# debug01.net
KiCad netlist of a schematic drawn in EAGLE
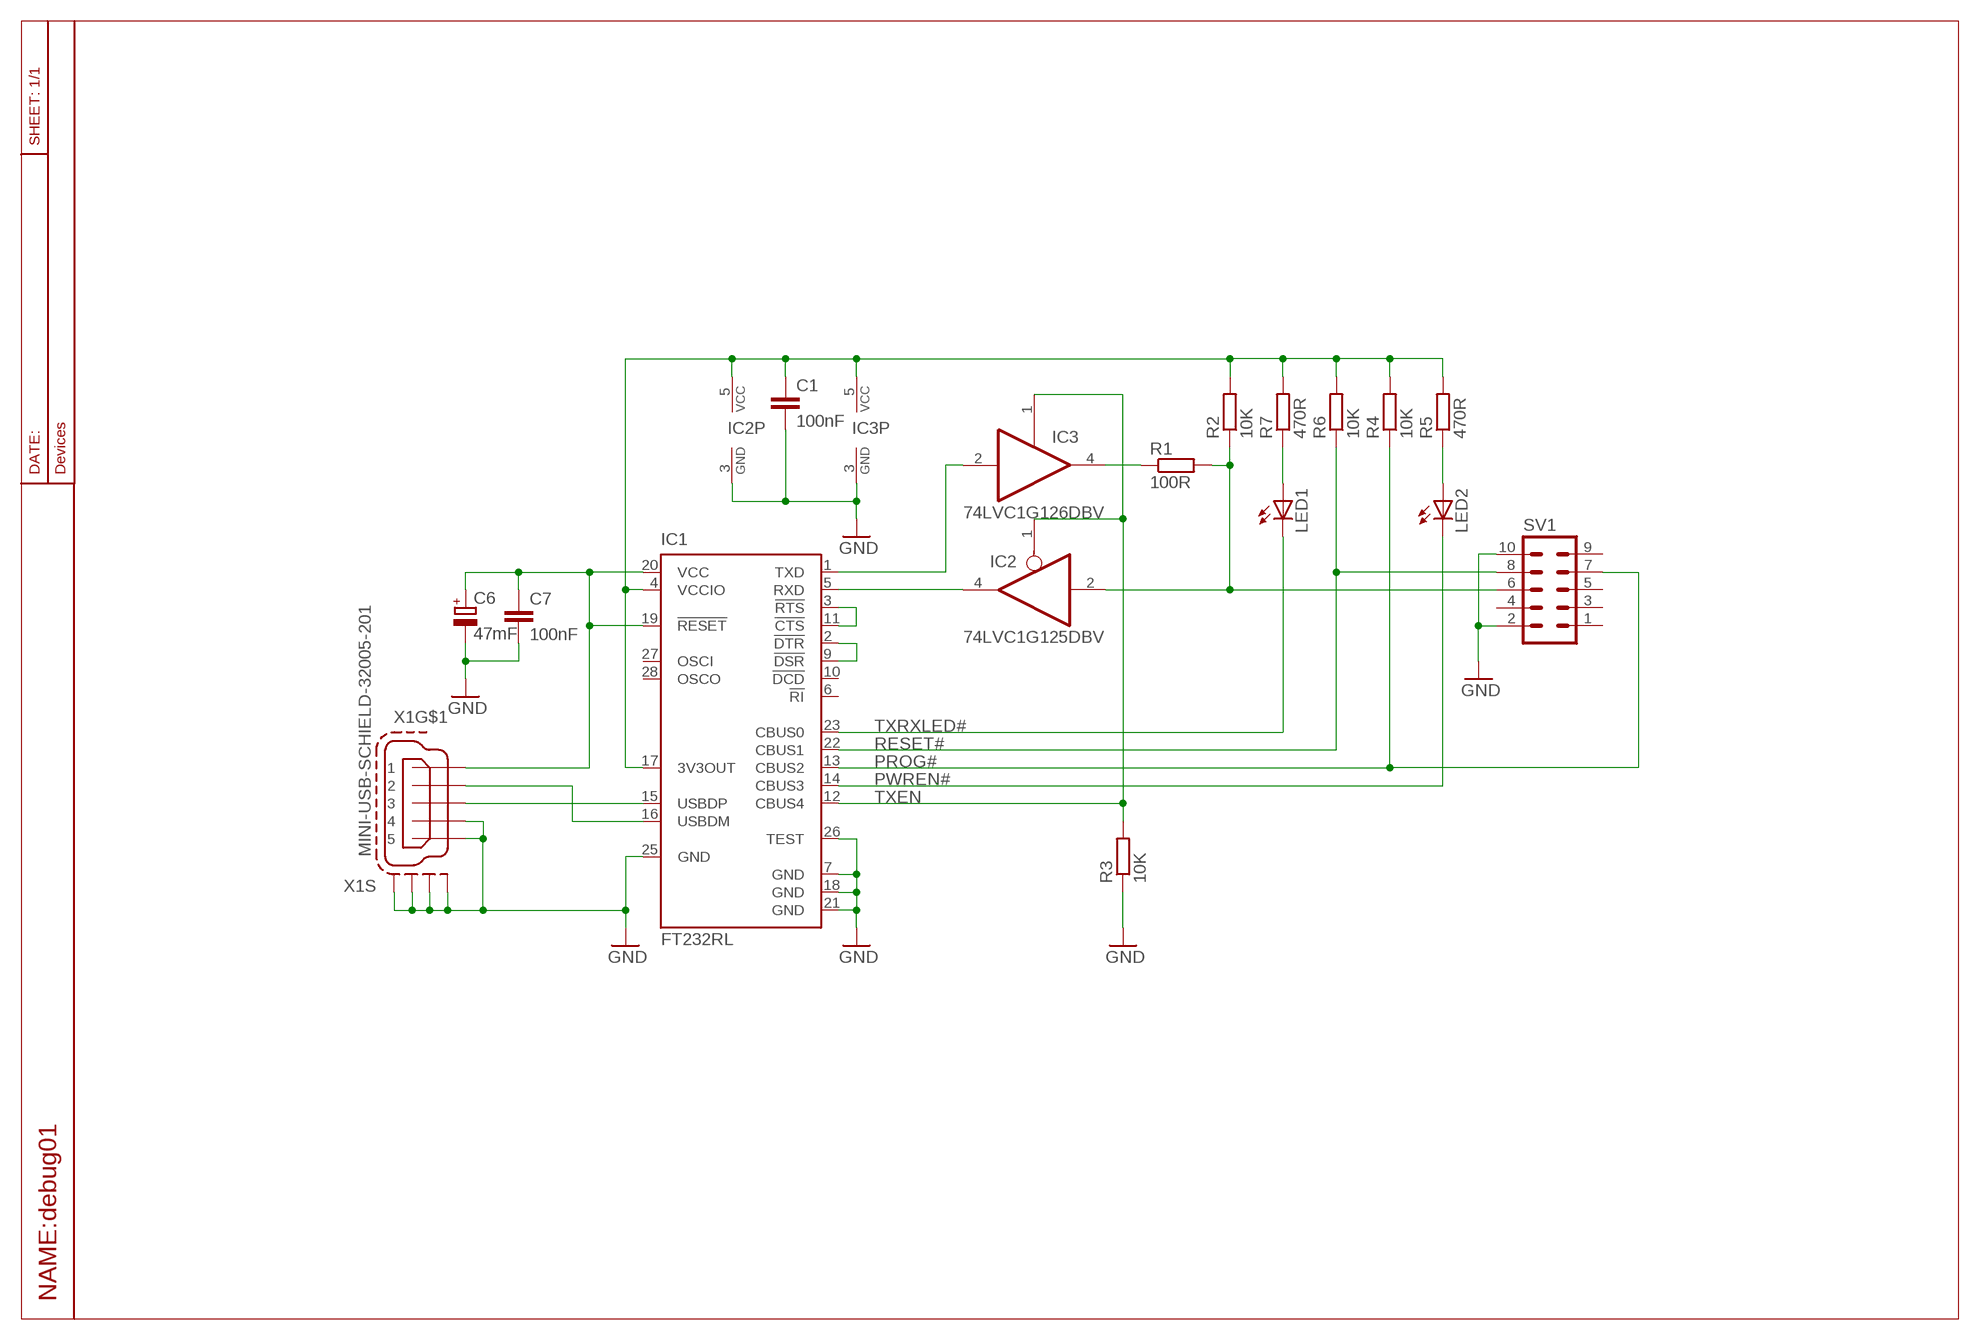
[diagram p0: schematic, sheet 1]

(export (version "E")
  (design (tool "Eeschema 10.0.6"))
  (components
    (comp (ref "C1")
      (value "100nF")
      (footprint "eagle-import:C0603")
      (libsource (lib "eagle-import") (part "C-EUC0603"))
    )
    (comp (ref "C6")
      (value "47mF")
      (footprint "eagle-import:CT3528")
      (libsource (lib "eagle-import") (part "CPOL-EUCT3528"))
    )
    (comp (ref "C7")
      (value "100nF")
      (footprint "eagle-import:C0603")
      (libsource (lib "eagle-import") (part "C-EUC0603"))
    )
    (comp (ref "IC1")
      (value "FT232RL")
      (footprint "eagle-import:SSOP28")
      (libsource (lib "eagle-import") (part "FT232RL"))
    )
    (comp (ref "IC2")
      (value "74LVC1G125DBV")
      (footprint "eagle-import:SOT23-5")
      (libsource (lib "eagle-import") (part "741G125DBVLVC"))
    )
    (comp (ref "IC3")
      (value "74LVC1G126DBV")
      (footprint "eagle-import:SOT23-5")
      (libsource (lib "eagle-import") (part "741G126DBVLVC"))
    )
    (comp (ref "LED1")
      (value "LEDCHIPLED_0805")
      (footprint "eagle-import:CHIPLED_0805")
      (libsource (lib "eagle-import") (part "LEDCHIPLED_0805"))
    )
    (comp (ref "LED2")
      (value "LEDCHIPLED_0805")
      (footprint "eagle-import:CHIPLED_0805")
      (libsource (lib "eagle-import") (part "LEDCHIPLED_0805"))
    )
    (comp (ref "R1")
      (value "100R")
      (footprint "eagle-import:R0603")
      (libsource (lib "eagle-import") (part "R-EU_R0603"))
    )
    (comp (ref "R2")
      (value "10K")
      (footprint "eagle-import:R0603")
      (libsource (lib "eagle-import") (part "R-EU_R0603"))
    )
    (comp (ref "R3")
      (value "10K")
      (footprint "eagle-import:R1206")
      (libsource (lib "eagle-import") (part "R-EU_R1206"))
    )
    (comp (ref "R4")
      (value "10K")
      (footprint "eagle-import:R0603")
      (libsource (lib "eagle-import") (part "R-EU_R0603"))
    )
    (comp (ref "R5")
      (value "470R")
      (footprint "eagle-import:R0603")
      (libsource (lib "eagle-import") (part "R-EU_R0603"))
    )
    (comp (ref "R6")
      (value "10K")
      (footprint "eagle-import:R0603")
      (libsource (lib "eagle-import") (part "R-EU_R0603"))
    )
    (comp (ref "R7")
      (value "470R")
      (footprint "eagle-import:R0603")
      (libsource (lib "eagle-import") (part "R-EU_R0603"))
    )
    (comp (ref "SV1")
      (value "ML10")
      (footprint "eagle-import:ML10")
      (libsource (lib "eagle-import") (part "ML10"))
    )
    (comp (ref "X1")
      (value "MINI-USB-SCHIELD-32005-201")
      (footprint "eagle-import:32005-201")
      (libsource (lib "eagle-import") (part "MINI-USB-SCHIELD-32005-201"))
    )
  )
  (nets
    (net (code "1") (name "/PROG#") (class "Default")
      (node (ref "IC1") (pin "13") (pinfunction "CBUS2_13") (pintype "bidirectional"))
      (node (ref "R4") (pin "1") (pinfunction "1_1") (pintype "passive"))
      (node (ref "SV1") (pin "7") (pinfunction "7_7") (pintype "passive"))
    )
    (net (code "2") (name "/PWREN#") (class "Default")
      (node (ref "IC1") (pin "14") (pinfunction "CBUS3_14") (pintype "bidirectional"))
      (node (ref "LED2") (pin "C") (pinfunction "C_C") (pintype "passive"))
    )
    (net (code "3") (name "/RESET#") (class "Default")
      (node (ref "IC1") (pin "22") (pinfunction "CBUS1_22") (pintype "bidirectional"))
      (node (ref "R6") (pin "1") (pinfunction "1_1") (pintype "passive"))
      (node (ref "SV1") (pin "8") (pinfunction "8_8") (pintype "passive"))
    )
    (net (code "4") (name "/TXEN") (class "Default")
      (node (ref "IC1") (pin "12") (pinfunction "CBUS4_12") (pintype "bidirectional"))
      (node (ref "IC2") (pin "1") (pinfunction "OE_1") (pintype "input"))
      (node (ref "IC3") (pin "1") (pinfunction "OE_1") (pintype "input"))
      (node (ref "R3") (pin "2") (pinfunction "2_2") (pintype "passive"))
    )
    (net (code "5") (name "/TXRXLED#") (class "Default")
      (node (ref "IC1") (pin "23") (pinfunction "CBUS0_23") (pintype "bidirectional"))
      (node (ref "LED1") (pin "C") (pinfunction "C_C") (pintype "passive"))
    )
    (net (code "6") (name "GND") (class "Default")
      (node (ref "C1") (pin "2") (pinfunction "2_2") (pintype "passive"))
      (node (ref "C6") (pin "-") (pinfunction "-_-") (pintype "passive"))
      (node (ref "C7") (pin "2") (pinfunction "2_2") (pintype "passive"))
      (node (ref "IC1") (pin "18") (pinfunction "GND_18") (pintype "power_in"))
      (node (ref "IC1") (pin "21") (pinfunction "GND_21") (pintype "power_in"))
      (node (ref "IC1") (pin "25") (pinfunction "GND_25") (pintype "power_in"))
      (node (ref "IC1") (pin "26") (pinfunction "TEST_26") (pintype "input"))
      (node (ref "IC1") (pin "7") (pinfunction "GND_7") (pintype "power_in"))
      (node (ref "IC2") (pin "3") (pinfunction "GND_3") (pintype "power_in"))
      (node (ref "IC3") (pin "3") (pinfunction "GND_3") (pintype "power_in"))
      (node (ref "R3") (pin "1") (pinfunction "1_1") (pintype "passive"))
      (node (ref "SV1") (pin "10") (pinfunction "10_10") (pintype "passive"))
      (node (ref "SV1") (pin "2") (pinfunction "2_2") (pintype "passive"))
      (node (ref "X1") (pin "4") (pinfunction "4_4") (pintype "passive"))
      (node (ref "X1") (pin "5") (pinfunction "5_5") (pintype "passive"))
      (node (ref "X1") (pin "M1") (pinfunction "S1_M1") (pintype "passive"))
      (node (ref "X1") (pin "M2") (pinfunction "S2_M2") (pintype "passive"))
      (node (ref "X1") (pin "M3") (pinfunction "S3_M3") (pintype "passive"))
      (node (ref "X1") (pin "M4") (pinfunction "S4_M4") (pintype "passive"))
    )
    (net (code "7") (name "Net-(IC1-3V3OUT)") (class "Default")
      (node (ref "C1") (pin "1") (pinfunction "1_1") (pintype "passive"))
      (node (ref "IC1") (pin "17") (pinfunction "3V3OUT_17") (pintype "output"))
      (node (ref "IC1") (pin "4") (pinfunction "VCCIO_4") (pintype "power_in"))
      (node (ref "IC2") (pin "5") (pinfunction "VCC_5") (pintype "power_in"))
      (node (ref "IC3") (pin "5") (pinfunction "VCC_5") (pintype "power_in"))
      (node (ref "R2") (pin "2") (pinfunction "2_2") (pintype "passive"))
      (node (ref "R4") (pin "2") (pinfunction "2_2") (pintype "passive"))
      (node (ref "R5") (pin "2") (pinfunction "2_2") (pintype "passive"))
      (node (ref "R6") (pin "2") (pinfunction "2_2") (pintype "passive"))
      (node (ref "R7") (pin "2") (pinfunction "2_2") (pintype "passive"))
    )
    (net (code "8") (name "Net-(IC1-RXD)") (class "Default")
      (node (ref "IC1") (pin "5") (pinfunction "RXD_5") (pintype "input"))
      (node (ref "IC2") (pin "4") (pinfunction "O_4") (pintype "tri_state"))
    )
    (net (code "9") (name "Net-(IC1-TXD)") (class "Default")
      (node (ref "IC1") (pin "1") (pinfunction "TXD_1") (pintype "output"))
      (node (ref "IC3") (pin "2") (pinfunction "I_2") (pintype "input"))
    )
    (net (code "10") (name "Net-(IC1-USBDM)") (class "Default")
      (node (ref "IC1") (pin "16") (pinfunction "USBDM_16") (pintype "bidirectional"))
      (node (ref "X1") (pin "2") (pinfunction "2_2") (pintype "passive"))
    )
    (net (code "11") (name "Net-(IC1-USBDP)") (class "Default")
      (node (ref "IC1") (pin "15") (pinfunction "USBDP_15") (pintype "bidirectional"))
      (node (ref "X1") (pin "3") (pinfunction "3_3") (pintype "passive"))
    )
    (net (code "12") (name "Net-(IC1-VCC)") (class "Default")
      (node (ref "C6") (pin "+") (pinfunction "+_+") (pintype "passive"))
      (node (ref "C7") (pin "1") (pinfunction "1_1") (pintype "passive"))
      (node (ref "IC1") (pin "19") (pinfunction "~{RESET}_19") (pintype "input"))
      (node (ref "IC1") (pin "20") (pinfunction "VCC_20") (pintype "power_in"))
      (node (ref "X1") (pin "1") (pinfunction "1_1") (pintype "passive"))
    )
    (net (code "13") (name "Net-(IC1-~{CTS})") (class "Default")
      (node (ref "IC1") (pin "11") (pinfunction "~{CTS}_11") (pintype "input"))
      (node (ref "IC1") (pin "3") (pinfunction "~{RTS}_3") (pintype "output"))
    )
    (net (code "14") (name "Net-(IC1-~{DSR})") (class "Default")
      (node (ref "IC1") (pin "2") (pinfunction "~{DTR}_2") (pintype "output"))
      (node (ref "IC1") (pin "9") (pinfunction "~{DSR}_9") (pintype "input"))
    )
    (net (code "15") (name "Net-(IC2A-I)") (class "Default")
      (node (ref "IC2") (pin "2") (pinfunction "I_2") (pintype "input"))
      (node (ref "R1") (pin "2") (pinfunction "2_2") (pintype "passive"))
      (node (ref "R2") (pin "1") (pinfunction "1_1") (pintype "passive"))
      (node (ref "SV1") (pin "6") (pinfunction "6_6") (pintype "passive"))
    )
    (net (code "16") (name "Net-(IC3A-O)") (class "Default")
      (node (ref "IC3") (pin "4") (pinfunction "O_4") (pintype "output"))
      (node (ref "R1") (pin "1") (pinfunction "1_1") (pintype "passive"))
    )
    (net (code "17") (name "Net-(LED1-PadA)") (class "Default")
      (node (ref "LED1") (pin "A") (pinfunction "A_A") (pintype "passive"))
      (node (ref "R7") (pin "1") (pinfunction "1_1") (pintype "passive"))
    )
    (net (code "18") (name "Net-(LED2-PadA)") (class "Default")
      (node (ref "LED2") (pin "A") (pinfunction "A_A") (pintype "passive"))
      (node (ref "R5") (pin "1") (pinfunction "1_1") (pintype "passive"))
    )
    (net (code "19") (name "unconnected-(IC1-OSCI-Pad27)") (class "Default")
      (node (ref "IC1") (pin "27") (pinfunction "OSCI_27") (pintype "input"))
    )
    (net (code "20") (name "unconnected-(IC1-OSCO-Pad28)") (class "Default")
      (node (ref "IC1") (pin "28") (pinfunction "OSCO_28") (pintype "output"))
    )
    (net (code "21") (name "unconnected-(IC1-~{DCD}-Pad10)") (class "Default")
      (node (ref "IC1") (pin "10") (pinfunction "~{DCD}_10") (pintype "input"))
    )
    (net (code "22") (name "unconnected-(IC1-~{RI}-Pad6)") (class "Default")
      (node (ref "IC1") (pin "6") (pinfunction "~{RI}_6") (pintype "input"))
    )
    (net (code "23") (name "unconnected-(SV1-Pad1)") (class "Default")
      (node (ref "SV1") (pin "1") (pinfunction "1_1") (pintype "passive"))
    )
    (net (code "24") (name "unconnected-(SV1-Pad3)") (class "Default")
      (node (ref "SV1") (pin "3") (pinfunction "3_3") (pintype "passive"))
    )
    (net (code "25") (name "unconnected-(SV1-Pad4)") (class "Default")
      (node (ref "SV1") (pin "4") (pinfunction "4_4") (pintype "passive"))
    )
    (net (code "26") (name "unconnected-(SV1-Pad5)") (class "Default")
      (node (ref "SV1") (pin "5") (pinfunction "5_5") (pintype "passive"))
    )
    (net (code "27") (name "unconnected-(SV1-Pad9)") (class "Default")
      (node (ref "SV1") (pin "9") (pinfunction "9_9") (pintype "passive"))
    )
  )
)
